# Isolation_Unit.net
KiCad netlist of a schematic drawn in Altium Designer
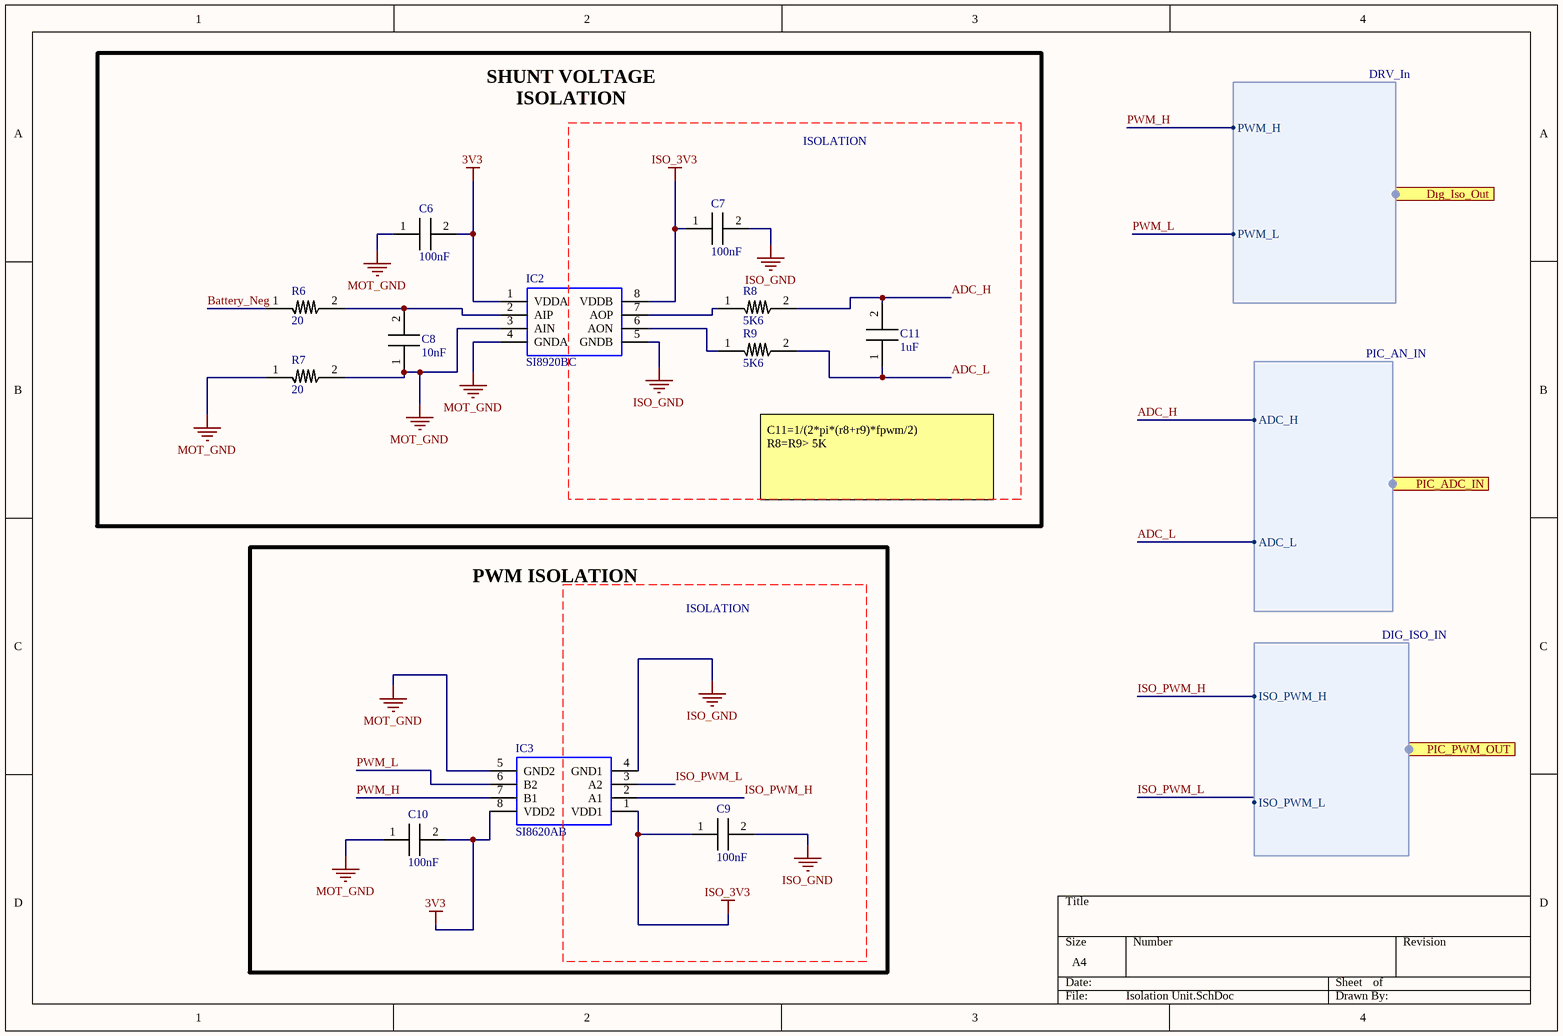
[diagram p0: Isolation Unit.SchDoc]

(export (version "E")
  (design (tool "Eeschema 10.0.6"))
  (components
    (comp (ref "C6")
      (value "CAP 100nF")
      (fields (field (name "PARAMETER 1") "100nF"))
      (libsource (lib "Schlib1") (part "CAP 100nF"))
    )
    (comp (ref "C7")
      (value "CAP 100nF")
      (fields (field (name "PARAMETER 1") "100nF"))
      (libsource (lib "Schlib1") (part "CAP 100nF"))
    )
    (comp (ref "C8")
      (value "CAP 10nF")
      (fields (field (name "PARAMETER 1") "10nF"))
      (libsource (lib "Schlib1") (part "CAP 10nF"))
    )
    (comp (ref "C9")
      (value "CAP 100nF")
      (fields (field (name "PARAMETER 1") "100nF"))
      (libsource (lib "Schlib1") (part "CAP 100nF"))
    )
    (comp (ref "C10")
      (value "CAP 100nF")
      (fields (field (name "PARAMETER 1") "100nF"))
      (libsource (lib "Schlib1") (part "CAP 100nF"))
    )
    (comp (ref "C11")
      (value "CAP 1uF")
      (fields (field (name "PARAMETER 1") "1uF"))
      (libsource (lib "Schlib1") (part "CAP 1uF"))
    )
    (comp (ref "IC2")
      (value "SI8920BC")
      (footprint "SI8920BC-IP")
      (libsource (lib "Schlib1") (part "IC ISO OP-AMP,SI8920BC"))
    )
    (comp (ref "IC3")
      (value "SI8620AB")
      (footprint "SI8620AB")
      (libsource (lib "Schlib1") (part "IC ISO DIG, SI8620AB"))
    )
    (comp (ref "R6")
      (value "RES, 20, 0603")
      (fields (field (name "PARAMETER 1") "20"))
      (libsource (lib "Schlib1") (part "RES, 20, 0603"))
    )
    (comp (ref "R7")
      (value "RES, 20, 0603")
      (fields (field (name "PARAMETER 1") "20"))
      (libsource (lib "Schlib1") (part "RES, 20, 0603"))
    )
    (comp (ref "R8")
      (value "RES, 5K6, 0603")
      (fields (field (name "PARAMETER 1") "5K6"))
      (libsource (lib "Schlib1") (part "RES, 5K6, 0603"))
    )
    (comp (ref "R9")
      (value "RES, 5K6, 0603")
      (fields (field (name "PARAMETER 1") "5K6"))
      (libsource (lib "Schlib1") (part "RES, 5K6, 0603"))
    )
  )
  (nets
    (net (code "4") (name "/ADC_H") (class "Default")
      (node (ref "C11") (pin "2") (pinfunction "2_2") (pintype "passive"))
      (node (ref "R8") (pin "2") (pinfunction "2_2") (pintype "passive"))
    )
    (net (code "5") (name "/ADC_L") (class "Default")
      (node (ref "C11") (pin "1") (pinfunction "1_1") (pintype "passive"))
      (node (ref "R9") (pin "2") (pinfunction "2_2") (pintype "passive"))
    )
    (net (code "6") (name "/Battery_Neg") (class "Default")
      (node (ref "R6") (pin "1") (pinfunction "1_1") (pintype "passive"))
    )
    (net (code "7") (name "/ISO_PWM_H") (class "Default")
      (node (ref "IC3") (pin "2") (pinfunction "A1_2") (pintype "passive"))
    )
    (net (code "8") (name "/ISO_PWM_L") (class "Default")
      (node (ref "IC3") (pin "3") (pinfunction "A2_3") (pintype "passive"))
    )
    (net (code "9") (name "/PWM_H") (class "Default")
      (node (ref "IC3") (pin "7") (pinfunction "B1_7") (pintype "passive"))
    )
    (net (code "10") (name "/PWM_L") (class "Default")
      (node (ref "IC3") (pin "6") (pinfunction "B2_6") (pintype "passive"))
    )
    (net (code "14") (name "3V3") (class "Default")
      (node (ref "C10") (pin "2") (pinfunction "2_2") (pintype "passive"))
      (node (ref "C6") (pin "2") (pinfunction "2_2") (pintype "passive"))
      (node (ref "IC2") (pin "1") (pinfunction "VDDA_1") (pintype "power_in"))
      (node (ref "IC3") (pin "8") (pinfunction "VDD2_8") (pintype "power_in"))
    )
    (net (code "15") (name "ISO_3V3") (class "Default")
      (node (ref "C7") (pin "1") (pinfunction "1_1") (pintype "passive"))
      (node (ref "C9") (pin "1") (pinfunction "1_1") (pintype "passive"))
      (node (ref "IC2") (pin "8") (pinfunction "VDDB_8") (pintype "power_in"))
      (node (ref "IC3") (pin "1") (pinfunction "VDD1_1") (pintype "power_in"))
    )
    (net (code "16") (name "ISO_GND") (class "Default")
      (node (ref "C7") (pin "2") (pinfunction "2_2") (pintype "passive"))
      (node (ref "C9") (pin "2") (pinfunction "2_2") (pintype "passive"))
      (node (ref "IC2") (pin "5") (pinfunction "GNDB_5") (pintype "passive"))
      (node (ref "IC3") (pin "4") (pinfunction "GND1_4") (pintype "passive"))
    )
    (net (code "17") (name "MOT_GND") (class "Default")
      (node (ref "C10") (pin "1") (pinfunction "1_1") (pintype "passive"))
      (node (ref "C6") (pin "1") (pinfunction "1_1") (pintype "passive"))
      (node (ref "C8") (pin "1") (pinfunction "1_1") (pintype "passive"))
      (node (ref "IC2") (pin "3") (pinfunction "AIN_3") (pintype "passive"))
      (node (ref "IC2") (pin "4") (pinfunction "GNDA_4") (pintype "passive"))
      (node (ref "IC3") (pin "5") (pinfunction "GND2_5") (pintype "passive"))
      (node (ref "R7") (pin "1") (pinfunction "1_1") (pintype "passive"))
      (node (ref "R7") (pin "2") (pinfunction "2_2") (pintype "passive"))
    )
    (net (code "18") (name "Net-(IC2-AIP)") (class "Default")
      (node (ref "C8") (pin "2") (pinfunction "2_2") (pintype "passive"))
      (node (ref "IC2") (pin "2") (pinfunction "AIP_2") (pintype "passive"))
      (node (ref "R6") (pin "2") (pinfunction "2_2") (pintype "passive"))
    )
    (net (code "19") (name "Net-(IC2-AON)") (class "Default")
      (node (ref "IC2") (pin "6") (pinfunction "AON_6") (pintype "passive"))
      (node (ref "R9") (pin "1") (pinfunction "1_1") (pintype "passive"))
    )
    (net (code "20") (name "Net-(IC2-AOP)") (class "Default")
      (node (ref "IC2") (pin "7") (pinfunction "AOP_7") (pintype "passive"))
      (node (ref "R8") (pin "1") (pinfunction "1_1") (pintype "passive"))
    )
  )
)
